# design.net
KiCad netlist of a schematic drawn in EasyEDA
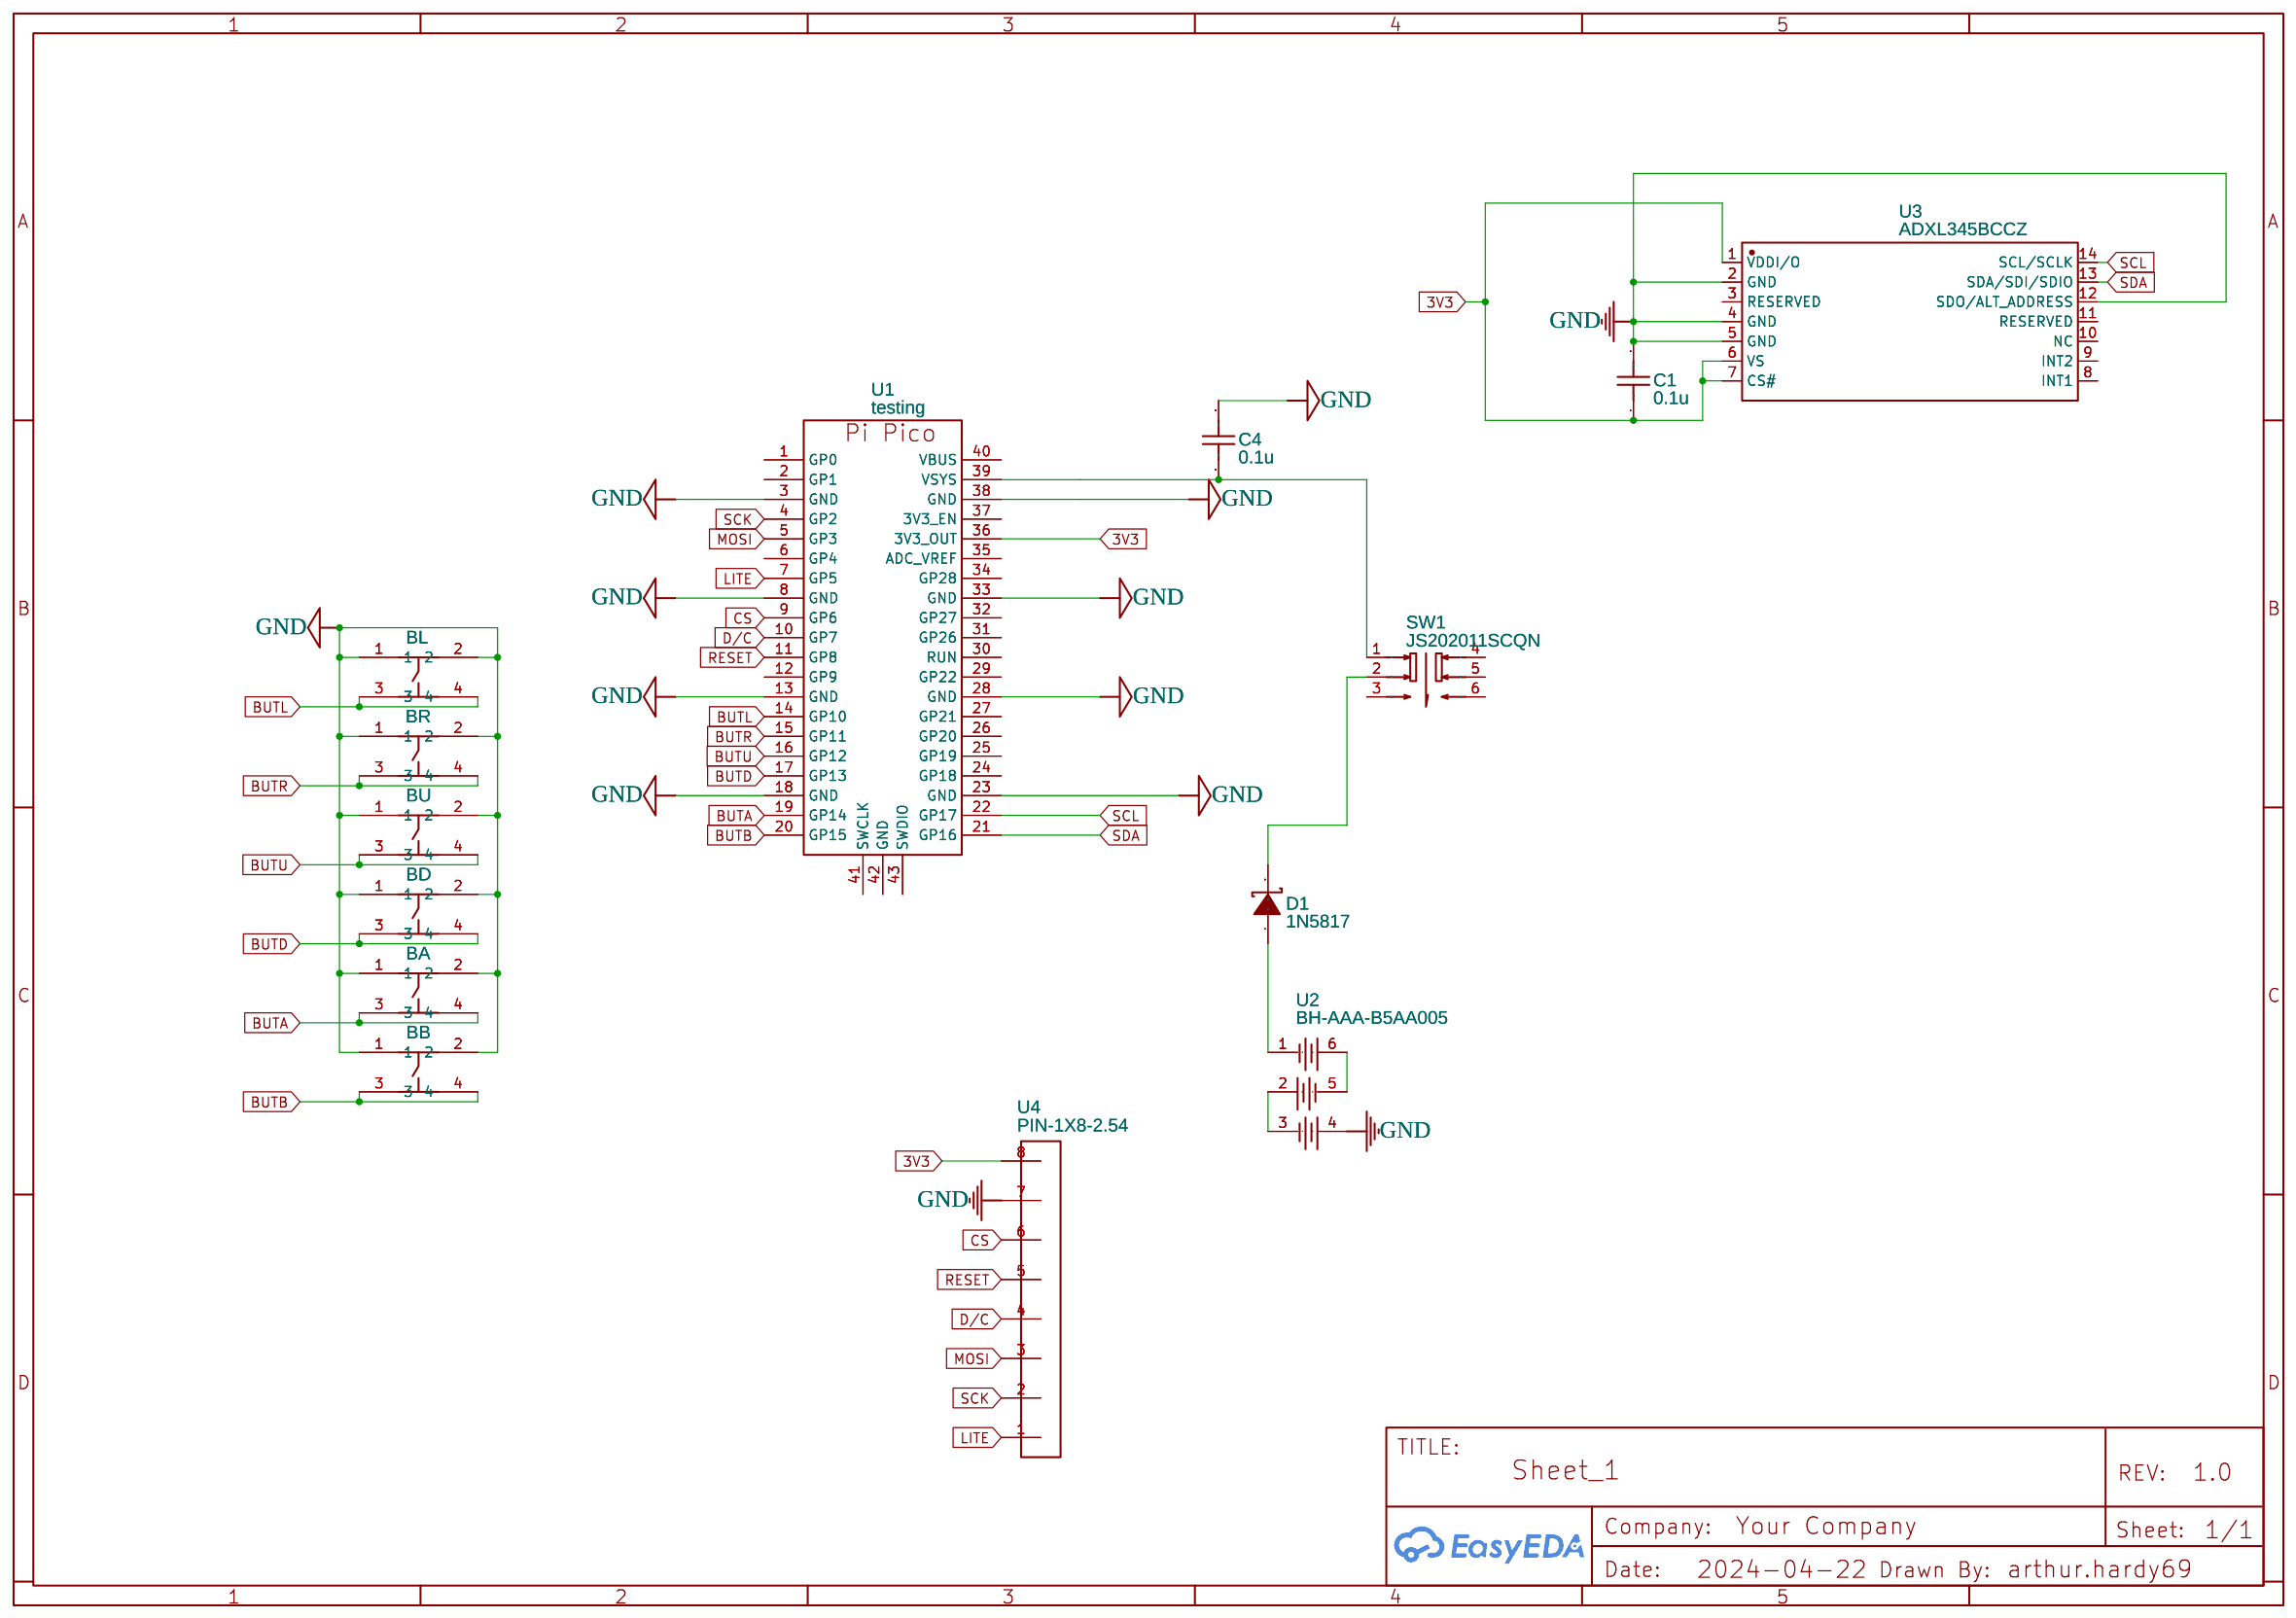
[diagram p0: schematic sheet]

(export (version "E")
  (design (tool "Eeschema 10.0.6"))
  (components
    (comp (ref "BA")
      (value "A")
      (fields (field (name "Manufacturer Part") "3101") (field (name "Manufacturer") "Adafruit"))
      (libsource (lib "") (part "Soft Tactile Button 8x8 (Adafruit 3101)_2"))
    )
    (comp (ref "BB")
      (value "B")
      (fields (field (name "Manufacturer Part") "3101") (field (name "Manufacturer") "Adafruit"))
      (libsource (lib "") (part "Soft Tactile Button 8x8 (Adafruit 3101)_5"))
    )
    (comp (ref "BD")
      (value "Down")
      (fields (field (name "Manufacturer Part") "3101") (field (name "Manufacturer") "Adafruit"))
      (libsource (lib "") (part "Soft Tactile Button 8x8 (Adafruit 3101)"))
    )
    (comp (ref "BL")
      (value "Left")
      (fields (field (name "Manufacturer Part") "3101") (field (name "Manufacturer") "Adafruit"))
      (libsource (lib "") (part "Soft Tactile Button 8x8 (Adafruit 3101)_1"))
    )
    (comp (ref "BR")
      (value "Right")
      (fields (field (name "Manufacturer Part") "3101") (field (name "Manufacturer") "Adafruit"))
      (libsource (lib "") (part "Soft Tactile Button 8x8 (Adafruit 3101)_3"))
    )
    (comp (ref "BU")
      (value "Up")
      (fields (field (name "Manufacturer Part") "3101") (field (name "Manufacturer") "Adafruit"))
      (libsource (lib "") (part "Soft Tactile Button 8x8 (Adafruit 3101)_4"))
    )
    (comp (ref "C1") (value "0.1u") (libsource (lib "") (part "C_0603_US")))
    (comp (ref "C4") (value "0.1u") (libsource (lib "") (part "C_0603_US")))
    (comp (ref "D1")
      (value "1N5817")
      (fields (field (name "Manufacturer") "MDD"))
      (libsource (lib "") (part "1N5817"))
    )
    (comp (ref "SW1")
      (value "JS202011SCQN")
      (fields (field (name "Manufacturer") "C&K"))
      (libsource (lib "") (part "JS202011SCQN"))
    )
    (comp (ref "U1")
      (value "testing")
      (fields
        (field (name "Manufacturer Part") "Pi Pico")
        (field (name "Manufacturer") "Raspberry Pi Foundation")
      )
      (libsource (lib "") (part "testing"))
    )
    (comp (ref "U2")
      (value "BH-AAA-B5AA005")
      (fields (field (name "Manufacturer") "MYOUNG(美阳)"))
      (libsource (lib "") (part "BH-AAA-B5AA005"))
    )
    (comp (ref "U3")
      (value "ADXL345BCCZ")
      (fields (field (name "Manufacturer") "ADI(亚德诺)"))
      (libsource (lib "") (part "ADXL345BCCZ"))
    )
    (comp (ref "U4") (value "PIN-1X8-2.54") (libsource (lib "") (part "PIN-1X8-2.54")))
  )
  (nets
    (net (code "1") (name "3V3") (class "Default")
      (node (ref "C1") (pin "1") (pinfunction "1_1") (pintype "unspecified"))
      (node (ref "U1") (pin "36") (pinfunction "3V3_OUT_36") (pintype "unspecified"))
      (node (ref "U3") (pin "1") (pinfunction "VDDI/O_1") (pintype "unspecified"))
      (node (ref "U3") (pin "6") (pinfunction "VS_6") (pintype "unspecified"))
      (node (ref "U3") (pin "7") (pinfunction "CS#_7") (pintype "unspecified"))
      (node (ref "U4") (pin "8") (pintype "unspecified"))
    )
    (net (code "2") (name "BUTA") (class "Default")
      (node (ref "BA") (pin "3") (pinfunction "3_3") (pintype "unspecified"))
      (node (ref "BA") (pin "4") (pinfunction "4_4") (pintype "unspecified"))
      (node (ref "U1") (pin "19") (pinfunction "GP14_19") (pintype "unspecified"))
    )
    (net (code "3") (name "BUTB") (class "Default")
      (node (ref "BB") (pin "3") (pinfunction "3_3") (pintype "unspecified"))
      (node (ref "BB") (pin "4") (pinfunction "4_4") (pintype "unspecified"))
      (node (ref "U1") (pin "20") (pinfunction "GP15_20") (pintype "unspecified"))
    )
    (net (code "4") (name "BUTD") (class "Default")
      (node (ref "BD") (pin "3") (pinfunction "3_3") (pintype "unspecified"))
      (node (ref "BD") (pin "4") (pinfunction "4_4") (pintype "unspecified"))
      (node (ref "U1") (pin "17") (pinfunction "GP13_17") (pintype "unspecified"))
    )
    (net (code "5") (name "BUTL") (class "Default")
      (node (ref "BL") (pin "3") (pinfunction "3_3") (pintype "unspecified"))
      (node (ref "BL") (pin "4") (pinfunction "4_4") (pintype "unspecified"))
      (node (ref "U1") (pin "14") (pinfunction "GP10_14") (pintype "unspecified"))
    )
    (net (code "6") (name "BUTR") (class "Default")
      (node (ref "BR") (pin "3") (pinfunction "3_3") (pintype "unspecified"))
      (node (ref "BR") (pin "4") (pinfunction "4_4") (pintype "unspecified"))
      (node (ref "U1") (pin "15") (pinfunction "GP11_15") (pintype "unspecified"))
    )
    (net (code "7") (name "BUTU") (class "Default")
      (node (ref "BU") (pin "3") (pinfunction "3_3") (pintype "unspecified"))
      (node (ref "BU") (pin "4") (pinfunction "4_4") (pintype "unspecified"))
      (node (ref "U1") (pin "16") (pinfunction "GP12_16") (pintype "unspecified"))
    )
    (net (code "8") (name "CS") (class "Default")
      (node (ref "U1") (pin "9") (pinfunction "GP6_9") (pintype "unspecified"))
      (node (ref "U4") (pin "6") (pintype "unspecified"))
    )
    (net (code "9") (name "D{slash}C") (class "Default")
      (node (ref "U1") (pin "10") (pinfunction "GP7_10") (pintype "unspecified"))
      (node (ref "U4") (pin "4") (pintype "unspecified"))
    )
    (net (code "10") (name "GND") (class "Default")
      (node (ref "BA") (pin "1") (pinfunction "1_1") (pintype "unspecified"))
      (node (ref "BA") (pin "2") (pinfunction "2_2") (pintype "unspecified"))
      (node (ref "BB") (pin "1") (pinfunction "1_1") (pintype "unspecified"))
      (node (ref "BB") (pin "2") (pinfunction "2_2") (pintype "unspecified"))
      (node (ref "BD") (pin "1") (pinfunction "1_1") (pintype "unspecified"))
      (node (ref "BD") (pin "2") (pinfunction "2_2") (pintype "unspecified"))
      (node (ref "BL") (pin "1") (pinfunction "1_1") (pintype "unspecified"))
      (node (ref "BL") (pin "2") (pinfunction "2_2") (pintype "unspecified"))
      (node (ref "BR") (pin "1") (pinfunction "1_1") (pintype "unspecified"))
      (node (ref "BR") (pin "2") (pinfunction "2_2") (pintype "unspecified"))
      (node (ref "BU") (pin "1") (pinfunction "1_1") (pintype "unspecified"))
      (node (ref "BU") (pin "2") (pinfunction "2_2") (pintype "unspecified"))
      (node (ref "C1") (pin "2") (pinfunction "2_2") (pintype "unspecified"))
      (node (ref "C4") (pin "2") (pinfunction "2_2") (pintype "unspecified"))
      (node (ref "U1") (pin "13") (pinfunction "GND_13") (pintype "unspecified"))
      (node (ref "U1") (pin "18") (pinfunction "GND_18") (pintype "unspecified"))
      (node (ref "U1") (pin "23") (pinfunction "GND_23") (pintype "unspecified"))
      (node (ref "U1") (pin "28") (pinfunction "GND_28") (pintype "unspecified"))
      (node (ref "U1") (pin "3") (pinfunction "GND_3") (pintype "unspecified"))
      (node (ref "U1") (pin "33") (pinfunction "GND_33") (pintype "unspecified"))
      (node (ref "U1") (pin "38") (pinfunction "GND_38") (pintype "unspecified"))
      (node (ref "U1") (pin "8") (pinfunction "GND_8") (pintype "unspecified"))
      (node (ref "U2") (pin "4") (pinfunction "+_4") (pintype "input"))
      (node (ref "U3") (pin "12") (pinfunction "SDO/ALT_ADDRESS_12") (pintype "unspecified"))
      (node (ref "U3") (pin "2") (pinfunction "GND_2") (pintype "unspecified"))
      (node (ref "U3") (pin "4") (pinfunction "GND_4") (pintype "unspecified"))
      (node (ref "U3") (pin "5") (pinfunction "GND_5") (pintype "unspecified"))
      (node (ref "U4") (pin "7") (pintype "unspecified"))
    )
    (net (code "11") (name "LITE") (class "Default")
      (node (ref "U1") (pin "7") (pinfunction "GP5_7") (pintype "unspecified"))
      (node (ref "U4") (pin "1") (pintype "unspecified"))
    )
    (net (code "12") (name "MOSI") (class "Default")
      (node (ref "U1") (pin "5") (pinfunction "GP3_5") (pintype "unspecified"))
      (node (ref "U4") (pin "3") (pintype "unspecified"))
    )
    (net (code "13") (name "Net-(D1-A)") (class "Default")
      (node (ref "D1") (pin "1") (pinfunction "A_1") (pintype "unspecified"))
      (node (ref "U2") (pin "1") (pinfunction "-_1") (pintype "input"))
    )
    (net (code "14") (name "Net-(D1-K)") (class "Default")
      (node (ref "D1") (pin "2") (pinfunction "K_2") (pintype "unspecified"))
      (node (ref "SW1") (pin "2") (pinfunction "2_2") (pintype "unspecified"))
    )
    (net (code "15") (name "Net-(U1-VSYS)") (class "Default")
      (node (ref "C4") (pin "1") (pinfunction "1_1") (pintype "unspecified"))
      (node (ref "SW1") (pin "1") (pinfunction "1_1") (pintype "unspecified"))
      (node (ref "U1") (pin "39") (pinfunction "VSYS_39") (pintype "unspecified"))
    )
    (net (code "16") (name "Net-(U2-+-Pad2)") (class "Default")
      (node (ref "U2") (pin "2") (pinfunction "+_2") (pintype "input"))
      (node (ref "U2") (pin "3") (pinfunction "-_3") (pintype "input"))
    )
    (net (code "17") (name "Net-(U2-+-Pad6)") (class "Default")
      (node (ref "U2") (pin "5") (pinfunction "-_5") (pintype "input"))
      (node (ref "U2") (pin "6") (pinfunction "+_6") (pintype "input"))
    )
    (net (code "18") (name "RESET") (class "Default")
      (node (ref "U1") (pin "11") (pinfunction "GP8_11") (pintype "unspecified"))
      (node (ref "U4") (pin "5") (pintype "unspecified"))
    )
    (net (code "19") (name "SCK") (class "Default")
      (node (ref "U1") (pin "4") (pinfunction "GP2_4") (pintype "unspecified"))
      (node (ref "U4") (pin "2") (pintype "unspecified"))
    )
    (net (code "20") (name "SCL") (class "Default")
      (node (ref "U1") (pin "22") (pinfunction "GP17_22") (pintype "unspecified"))
      (node (ref "U3") (pin "14") (pinfunction "SCL/SCLK_14") (pintype "unspecified"))
    )
    (net (code "21") (name "SDA") (class "Default")
      (node (ref "U1") (pin "21") (pinfunction "GP16_21") (pintype "unspecified"))
      (node (ref "U3") (pin "13") (pinfunction "SDA/SDI/SDIO_13") (pintype "unspecified"))
    )
    (net (code "22") (name "unconnected-(SW1-Pad3)") (class "Default")
      (node (ref "SW1") (pin "3") (pinfunction "3_3") (pintype "unspecified"))
    )
    (net (code "23") (name "unconnected-(SW1-Pad4)") (class "Default")
      (node (ref "SW1") (pin "4") (pinfunction "4_4") (pintype "unspecified"))
    )
    (net (code "24") (name "unconnected-(SW1-Pad5)") (class "Default")
      (node (ref "SW1") (pin "5") (pinfunction "5_5") (pintype "unspecified"))
    )
    (net (code "25") (name "unconnected-(SW1-Pad6)") (class "Default")
      (node (ref "SW1") (pin "6") (pinfunction "6_6") (pintype "unspecified"))
    )
    (net (code "26") (name "unconnected-(U1-3V3_EN-Pad37)") (class "Default")
      (node (ref "U1") (pin "37") (pinfunction "3V3_EN_37") (pintype "unspecified"))
    )
    (net (code "27") (name "unconnected-(U1-ADC_VREF-Pad35)") (class "Default")
      (node (ref "U1") (pin "35") (pinfunction "ADC_VREF_35") (pintype "unspecified"))
    )
    (net (code "28") (name "unconnected-(U1-GND-Pad42)") (class "Default")
      (node (ref "U1") (pin "42") (pinfunction "GND_42") (pintype "unspecified"))
    )
    (net (code "29") (name "unconnected-(U1-GP0-Pad1)") (class "Default")
      (node (ref "U1") (pin "1") (pinfunction "GP0_1") (pintype "unspecified"))
    )
    (net (code "30") (name "unconnected-(U1-GP1-Pad2)") (class "Default")
      (node (ref "U1") (pin "2") (pinfunction "GP1_2") (pintype "unspecified"))
    )
    (net (code "31") (name "unconnected-(U1-GP4-Pad6)") (class "Default")
      (node (ref "U1") (pin "6") (pinfunction "GP4_6") (pintype "unspecified"))
    )
    (net (code "32") (name "unconnected-(U1-GP9-Pad12)") (class "Default")
      (node (ref "U1") (pin "12") (pinfunction "GP9_12") (pintype "unspecified"))
    )
    (net (code "33") (name "unconnected-(U1-GP18-Pad24)") (class "Default")
      (node (ref "U1") (pin "24") (pinfunction "GP18_24") (pintype "unspecified"))
    )
    (net (code "34") (name "unconnected-(U1-GP19-Pad25)") (class "Default")
      (node (ref "U1") (pin "25") (pinfunction "GP19_25") (pintype "unspecified"))
    )
    (net (code "35") (name "unconnected-(U1-GP20-Pad26)") (class "Default")
      (node (ref "U1") (pin "26") (pinfunction "GP20_26") (pintype "unspecified"))
    )
    (net (code "36") (name "unconnected-(U1-GP21-Pad27)") (class "Default")
      (node (ref "U1") (pin "27") (pinfunction "GP21_27") (pintype "unspecified"))
    )
    (net (code "37") (name "unconnected-(U1-GP22-Pad29)") (class "Default")
      (node (ref "U1") (pin "29") (pinfunction "GP22_29") (pintype "unspecified"))
    )
    (net (code "38") (name "unconnected-(U1-GP26-Pad31)") (class "Default")
      (node (ref "U1") (pin "31") (pinfunction "GP26_31") (pintype "unspecified"))
    )
    (net (code "39") (name "unconnected-(U1-GP27-Pad32)") (class "Default")
      (node (ref "U1") (pin "32") (pinfunction "GP27_32") (pintype "unspecified"))
    )
    (net (code "40") (name "unconnected-(U1-GP28-Pad34)") (class "Default")
      (node (ref "U1") (pin "34") (pinfunction "GP28_34") (pintype "unspecified"))
    )
    (net (code "41") (name "unconnected-(U1-RUN-Pad30)") (class "Default")
      (node (ref "U1") (pin "30") (pinfunction "RUN_30") (pintype "unspecified"))
    )
    (net (code "42") (name "unconnected-(U1-SWCLK-Pad41)") (class "Default")
      (node (ref "U1") (pin "41") (pinfunction "SWCLK_41") (pintype "unspecified"))
    )
    (net (code "43") (name "unconnected-(U1-SWDIO-Pad43)") (class "Default")
      (node (ref "U1") (pin "43") (pinfunction "SWDIO_43") (pintype "unspecified"))
    )
    (net (code "44") (name "unconnected-(U1-VBUS-Pad40)") (class "Default")
      (node (ref "U1") (pin "40") (pinfunction "VBUS_40") (pintype "unspecified"))
    )
    (net (code "45") (name "unconnected-(U3-INT1-Pad8)") (class "Default")
      (node (ref "U3") (pin "8") (pinfunction "INT1_8") (pintype "unspecified"))
    )
    (net (code "46") (name "unconnected-(U3-INT2-Pad9)") (class "Default")
      (node (ref "U3") (pin "9") (pinfunction "INT2_9") (pintype "unspecified"))
    )
    (net (code "47") (name "unconnected-(U3-NC-Pad10)") (class "Default")
      (node (ref "U3") (pin "10") (pinfunction "NC_10") (pintype "unspecified"))
    )
    (net (code "48") (name "unconnected-(U3-RESERVED-Pad3)") (class "Default")
      (node (ref "U3") (pin "3") (pinfunction "RESERVED_3") (pintype "unspecified"))
    )
    (net (code "49") (name "unconnected-(U3-RESERVED-Pad11)") (class "Default")
      (node (ref "U3") (pin "11") (pinfunction "RESERVED_11") (pintype "unspecified"))
    )
  )
)
